# CON_REVC.net
KiCad netlist of a schematic drawn in EAGLE
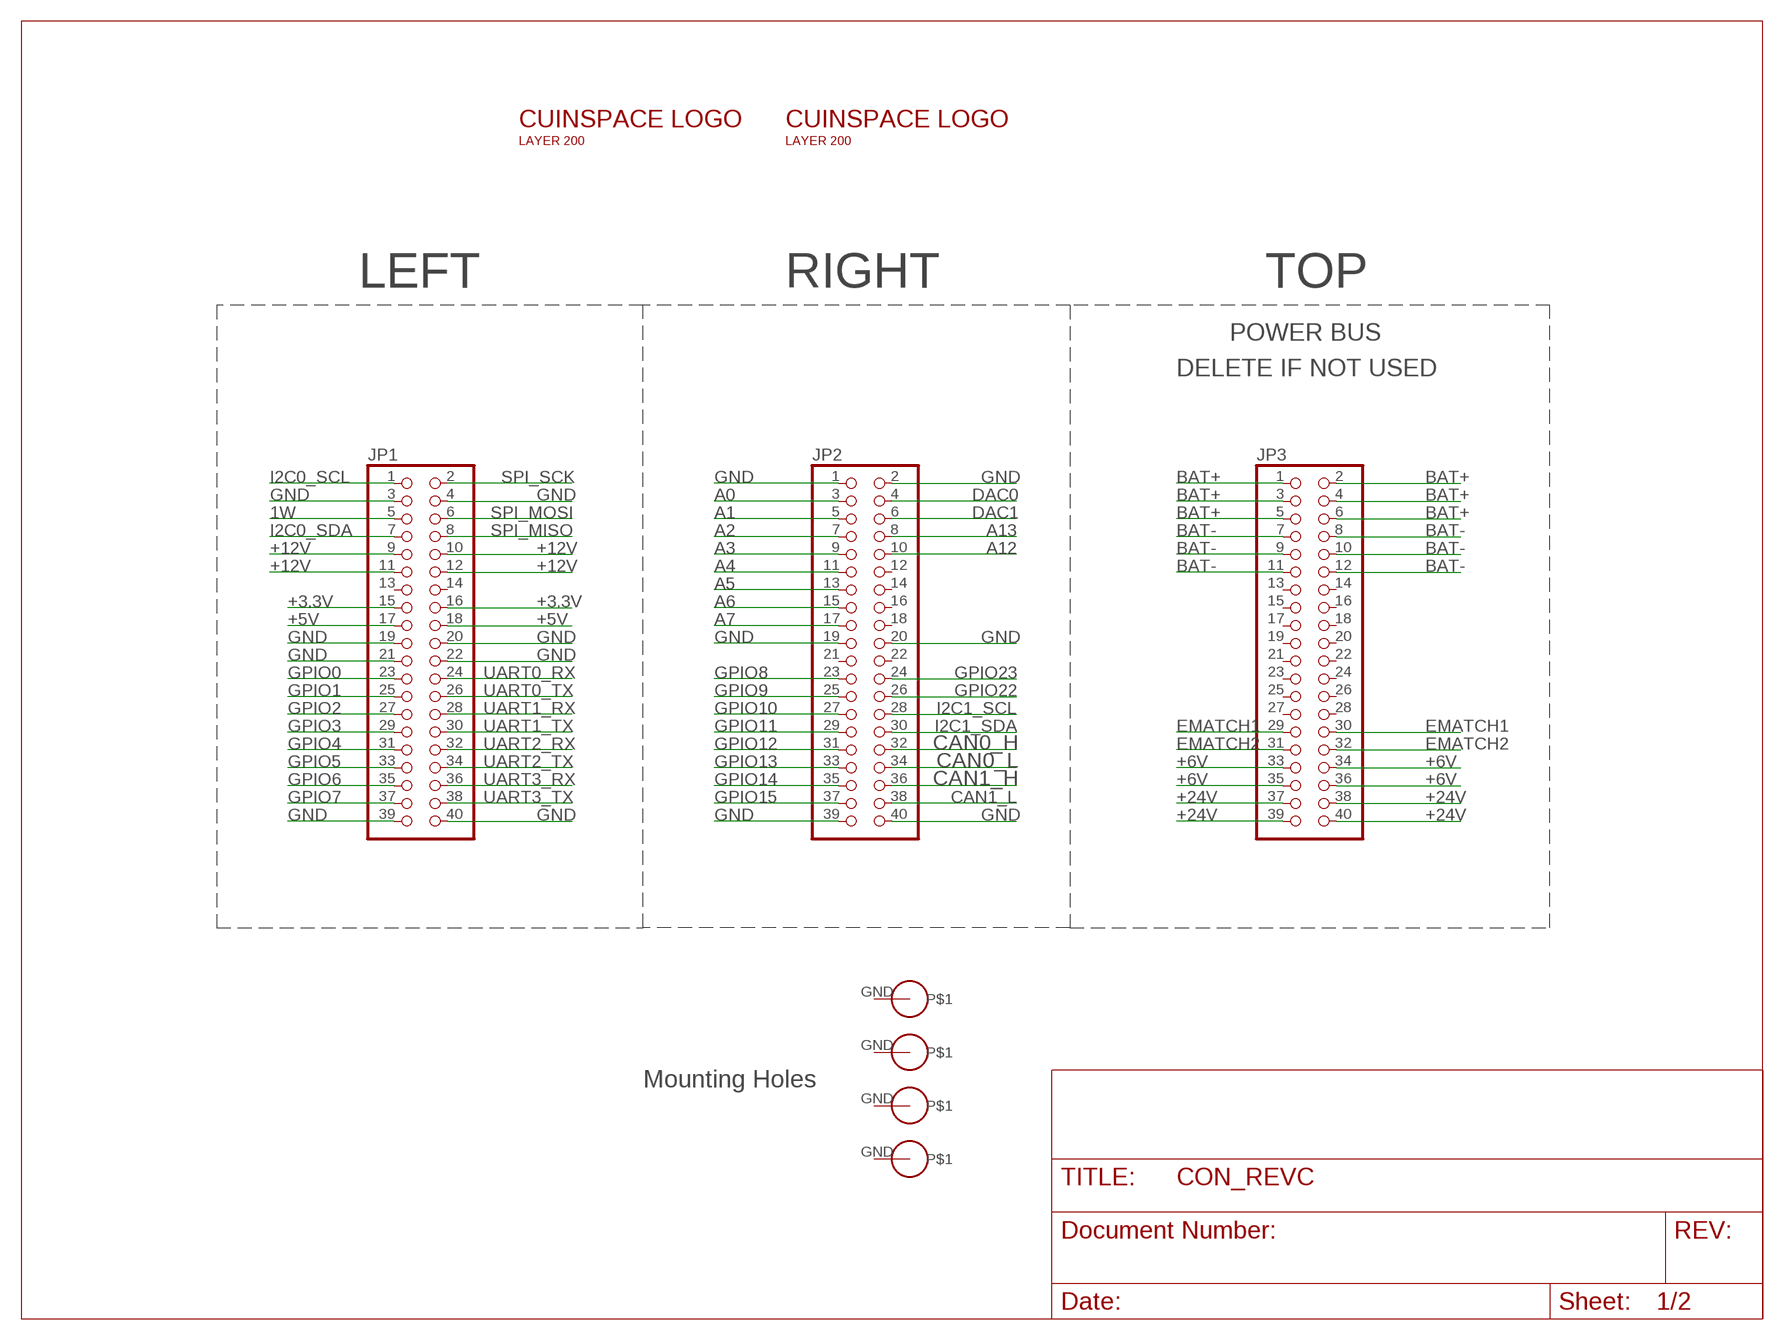
[diagram p0: schematic, sheet 1]
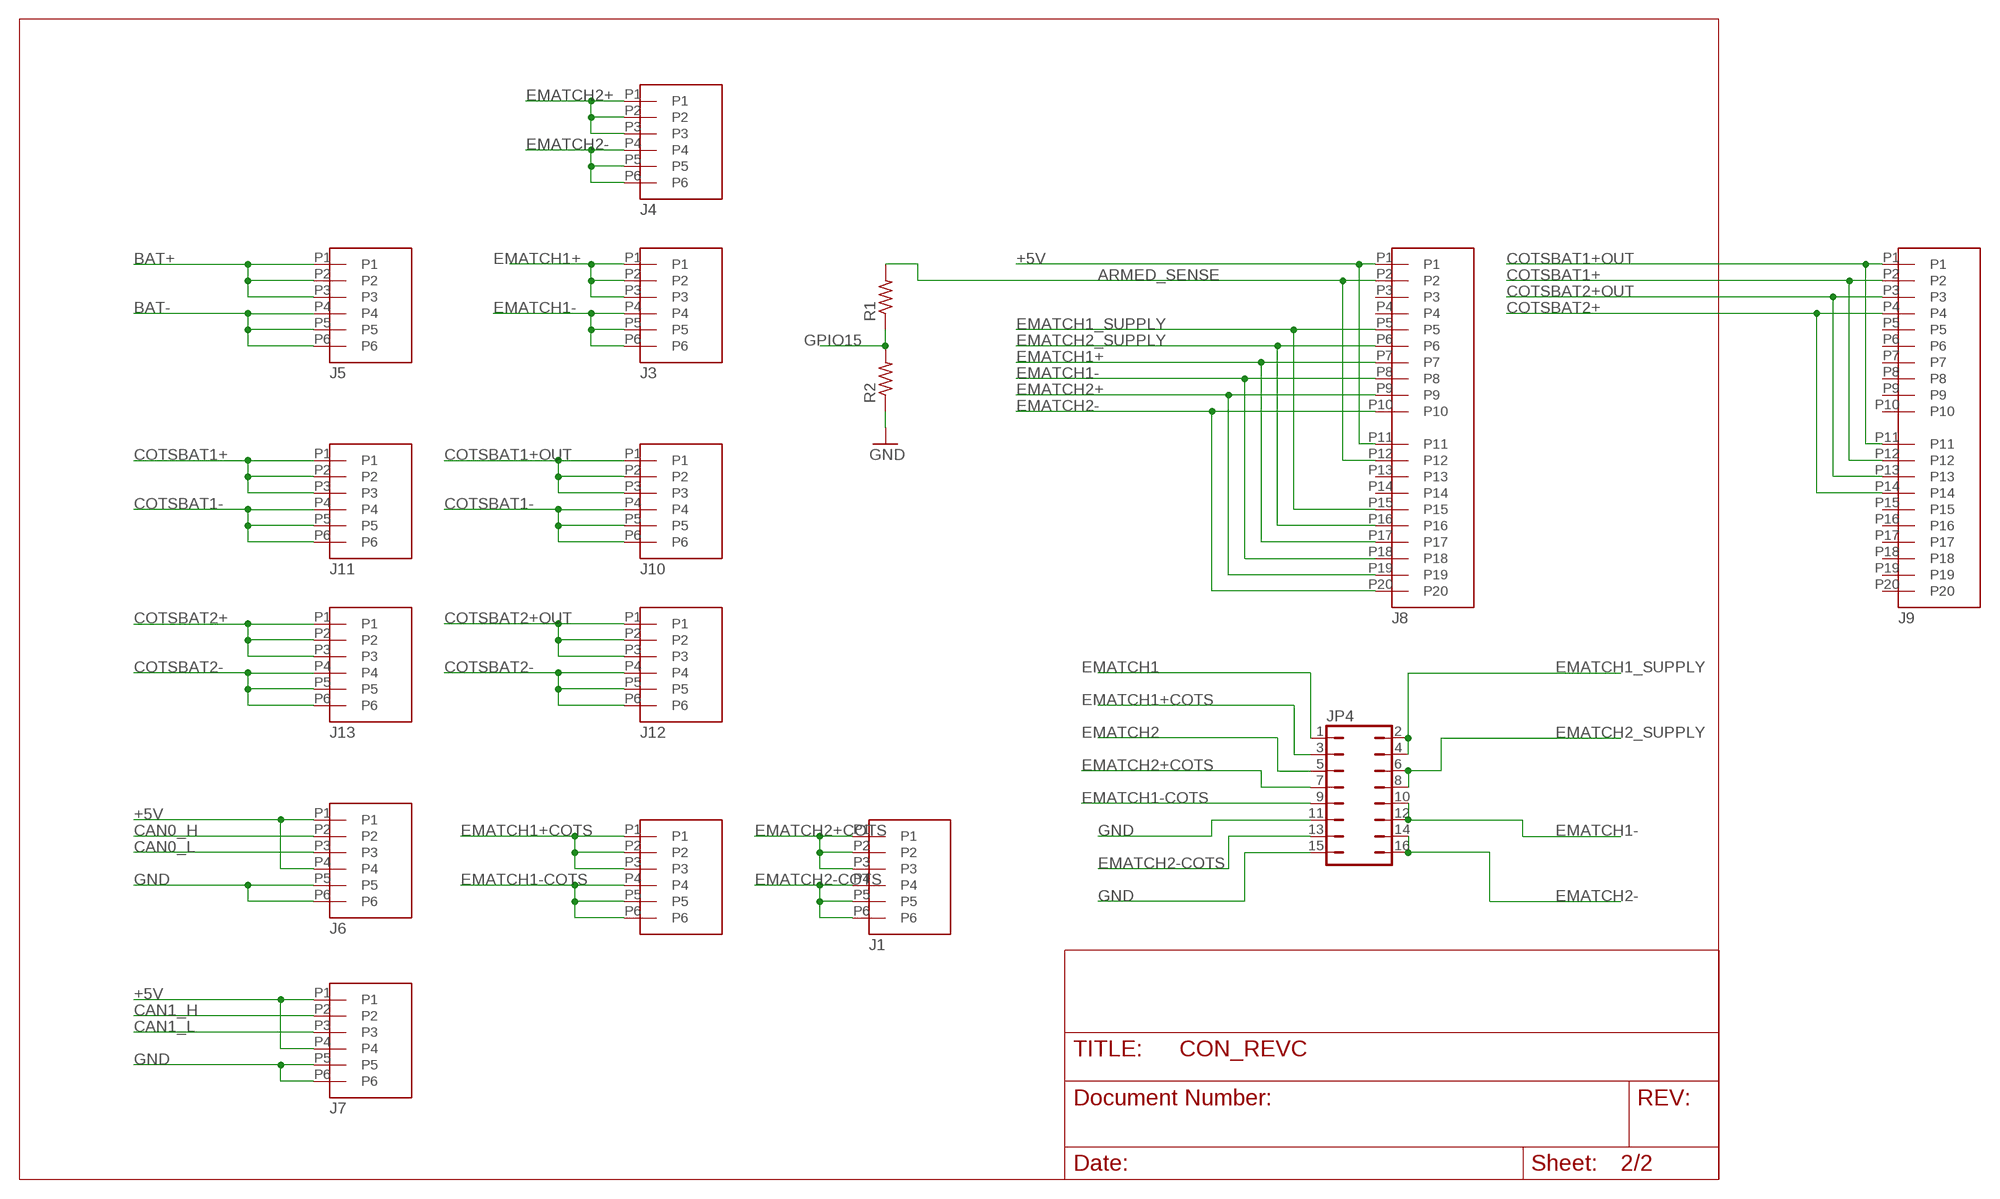
[diagram p1: schematic, sheet 2]

(export (version "E")
  (design (tool "Eeschema 10.0.6"))
  (components
    (comp (ref "$$U$1")
      (value "PS/104-MOUNTING-HOLE")
      (footprint "eagle-import:PC_104-MOUNTING-HOLE")
      (libsource (lib "eagle-import") (part "PS/104-MOUNTING-HOLE"))
    )
    (comp (ref "JP1")
      (value "PINHD-2X20")
      (footprint "eagle-import:2X20")
      (libsource (lib "eagle-import") (part "PINHD-2X20"))
    )
    (comp (ref "JP2")
      (value "PINHD-2X20")
      (footprint "eagle-import:2X20")
      (libsource (lib "eagle-import") (part "PINHD-2X20"))
    )
    (comp (ref "JP3")
      (value "PINHD-2X20")
      (footprint "eagle-import:2X20")
      (libsource (lib "eagle-import") (part "PINHD-2X20"))
    )
    (comp (ref "U$1")
      (value "PS/104-MOUNTING-HOLE")
      (footprint "eagle-import:PC_104-MOUNTING-HOLE")
      (libsource (lib "eagle-import") (part "PS/104-MOUNTING-HOLE"))
    )
    (comp (ref "U$2")
      (value "PS/104-MOUNTING-HOLE")
      (footprint "eagle-import:PC_104-MOUNTING-HOLE")
      (libsource (lib "eagle-import") (part "PS/104-MOUNTING-HOLE"))
    )
    (comp (ref "U$3")
      (value "PS/104-MOUNTING-HOLE")
      (footprint "eagle-import:PC_104-MOUNTING-HOLE")
      (libsource (lib "eagle-import") (part "PS/104-MOUNTING-HOLE"))
    )
    (comp (ref "U$5")
      (value "INSPACE3CM_L")
      (footprint "eagle-import:INSPACE_3CM_LETTERS")
      (libsource (lib "eagle-import") (part "INSPACE3CM_L"))
    )
    (comp (ref "U$6")
      (value "INSPACE3CM_L")
      (footprint "eagle-import:INSPACE_3CM_LETTERS")
      (libsource (lib "eagle-import") (part "INSPACE3CM_L"))
    )
    (comp (ref "J1")
      (value "M80-5100642")
      (footprint "eagle-import:M80-5100642")
      (libsource (lib "eagle-import") (part "M80-5100642"))
    )
    (comp (ref "J2")
      (value "M80-5100642")
      (footprint "eagle-import:M80-5100642")
      (libsource (lib "eagle-import") (part "M80-5100642"))
    )
    (comp (ref "J3")
      (value "M80-5100642")
      (footprint "eagle-import:M80-5100642")
      (libsource (lib "eagle-import") (part "M80-5100642"))
    )
    (comp (ref "J4")
      (value "M80-5100642")
      (footprint "eagle-import:M80-5100642")
      (libsource (lib "eagle-import") (part "M80-5100642"))
    )
    (comp (ref "J5")
      (value "M80-5100642")
      (footprint "eagle-import:M80-5100642")
      (libsource (lib "eagle-import") (part "M80-5100642"))
    )
    (comp (ref "J6")
      (value "M80-5100642")
      (footprint "eagle-import:M80-5100642")
      (libsource (lib "eagle-import") (part "M80-5100642"))
    )
    (comp (ref "J7")
      (value "M80-5100642")
      (footprint "eagle-import:M80-5100642")
      (libsource (lib "eagle-import") (part "M80-5100642"))
    )
    (comp (ref "J8")
      (value "M80-5102042")
      (footprint "eagle-import:M80-5102042")
      (libsource (lib "eagle-import") (part "M80-5102042"))
    )
    (comp (ref "J9")
      (value "M80-5102042")
      (footprint "eagle-import:M80-5102042")
      (libsource (lib "eagle-import") (part "M80-5102042"))
    )
    (comp (ref "J10")
      (value "M80-5100642")
      (footprint "eagle-import:M80-5100642")
      (libsource (lib "eagle-import") (part "M80-5100642"))
    )
    (comp (ref "J11")
      (value "M80-5100642")
      (footprint "eagle-import:M80-5100642")
      (libsource (lib "eagle-import") (part "M80-5100642"))
    )
    (comp (ref "J12")
      (value "M80-5100642")
      (footprint "eagle-import:M80-5100642")
      (libsource (lib "eagle-import") (part "M80-5100642"))
    )
    (comp (ref "J13")
      (value "M80-5100642")
      (footprint "eagle-import:M80-5100642")
      (libsource (lib "eagle-import") (part "M80-5100642"))
    )
    (comp (ref "JP4")
      (value "JP8Q")
      (footprint "eagle-import:JP8Q")
      (libsource (lib "eagle-import") (part "JP8Q"))
    )
    (comp (ref "R1")
      (value "R-US_R0805")
      (footprint "eagle-import:R0805")
      (libsource (lib "eagle-import") (part "R-US_R0805"))
    )
    (comp (ref "R2")
      (value "R-US_R0805")
      (footprint "eagle-import:R0805")
      (libsource (lib "eagle-import") (part "R-US_R0805"))
    )
  )
  (nets
    (net (code "1") (name "+3.3V") (class "Default")
      (node (ref "JP1") (pin "15") (pinfunction "15_15") (pintype "passive"))
      (node (ref "JP1") (pin "16") (pinfunction "16_16") (pintype "passive"))
    )
    (net (code "2") (name "+5V") (class "Default")
      (node (ref "J6") (pin "P1") (pinfunction "P1_P1") (pintype "bidirectional"))
      (node (ref "J6") (pin "P4") (pinfunction "P4_P4") (pintype "bidirectional"))
      (node (ref "J7") (pin "P1") (pinfunction "P1_P1") (pintype "bidirectional"))
      (node (ref "J7") (pin "P4") (pinfunction "P4_P4") (pintype "bidirectional"))
      (node (ref "J8") (pin "P1") (pinfunction "P1_P1") (pintype "bidirectional"))
      (node (ref "J8") (pin "P11") (pinfunction "P11_P11") (pintype "bidirectional"))
      (node (ref "JP1") (pin "17") (pinfunction "17_17") (pintype "passive"))
      (node (ref "JP1") (pin "18") (pinfunction "18_18") (pintype "passive"))
    )
    (net (code "3") (name "+6V") (class "Default")
      (node (ref "JP3") (pin "33") (pinfunction "33_33") (pintype "passive"))
      (node (ref "JP3") (pin "34") (pinfunction "34_34") (pintype "passive"))
      (node (ref "JP3") (pin "35") (pinfunction "35_35") (pintype "passive"))
      (node (ref "JP3") (pin "36") (pinfunction "36_36") (pintype "passive"))
    )
    (net (code "4") (name "+12V") (class "Default")
      (node (ref "JP1") (pin "10") (pinfunction "10_10") (pintype "passive"))
      (node (ref "JP1") (pin "11") (pinfunction "11_11") (pintype "passive"))
      (node (ref "JP1") (pin "12") (pinfunction "12_12") (pintype "passive"))
      (node (ref "JP1") (pin "9") (pinfunction "9_9") (pintype "passive"))
    )
    (net (code "5") (name "+24V") (class "Default")
      (node (ref "JP3") (pin "37") (pinfunction "37_37") (pintype "passive"))
      (node (ref "JP3") (pin "38") (pinfunction "38_38") (pintype "passive"))
      (node (ref "JP3") (pin "39") (pinfunction "39_39") (pintype "passive"))
      (node (ref "JP3") (pin "40") (pinfunction "40_40") (pintype "passive"))
    )
    (net (code "6") (name "1W") (class "Default")
      (node (ref "JP1") (pin "5") (pinfunction "5_5") (pintype "passive"))
    )
    (net (code "7") (name "A0") (class "Default")
      (node (ref "JP2") (pin "3") (pinfunction "3_3") (pintype "passive"))
    )
    (net (code "8") (name "A1") (class "Default")
      (node (ref "JP2") (pin "5") (pinfunction "5_5") (pintype "passive"))
    )
    (net (code "9") (name "A2") (class "Default")
      (node (ref "JP2") (pin "7") (pinfunction "7_7") (pintype "passive"))
    )
    (net (code "10") (name "A3") (class "Default")
      (node (ref "JP2") (pin "9") (pinfunction "9_9") (pintype "passive"))
    )
    (net (code "11") (name "A4") (class "Default")
      (node (ref "JP2") (pin "11") (pinfunction "11_11") (pintype "passive"))
    )
    (net (code "12") (name "A5") (class "Default")
      (node (ref "JP2") (pin "13") (pinfunction "13_13") (pintype "passive"))
    )
    (net (code "13") (name "A6") (class "Default")
      (node (ref "JP2") (pin "15") (pinfunction "15_15") (pintype "passive"))
    )
    (net (code "14") (name "A7") (class "Default")
      (node (ref "JP2") (pin "17") (pinfunction "17_17") (pintype "passive"))
    )
    (net (code "15") (name "A12") (class "Default")
      (node (ref "JP2") (pin "10") (pinfunction "10_10") (pintype "passive"))
    )
    (net (code "16") (name "A13") (class "Default")
      (node (ref "JP2") (pin "8") (pinfunction "8_8") (pintype "passive"))
    )
    (net (code "17") (name "ARMED_SENSE") (class "Default")
      (node (ref "J8") (pin "P12") (pinfunction "P12_P12") (pintype "bidirectional"))
      (node (ref "J8") (pin "P2") (pinfunction "P2_P2") (pintype "bidirectional"))
      (node (ref "R1") (pin "2") (pinfunction "2_2") (pintype "passive"))
    )
    (net (code "18") (name "BAT+") (class "Default")
      (node (ref "J5") (pin "P1") (pinfunction "P1_P1") (pintype "bidirectional"))
      (node (ref "J5") (pin "P2") (pinfunction "P2_P2") (pintype "bidirectional"))
      (node (ref "J5") (pin "P3") (pinfunction "P3_P3") (pintype "bidirectional"))
      (node (ref "JP3") (pin "1") (pinfunction "1_1") (pintype "passive"))
      (node (ref "JP3") (pin "2") (pinfunction "2_2") (pintype "passive"))
      (node (ref "JP3") (pin "3") (pinfunction "3_3") (pintype "passive"))
      (node (ref "JP3") (pin "4") (pinfunction "4_4") (pintype "passive"))
      (node (ref "JP3") (pin "5") (pinfunction "5_5") (pintype "passive"))
      (node (ref "JP3") (pin "6") (pinfunction "6_6") (pintype "passive"))
    )
    (net (code "19") (name "BAT-") (class "Default")
      (node (ref "J5") (pin "P4") (pinfunction "P4_P4") (pintype "bidirectional"))
      (node (ref "J5") (pin "P5") (pinfunction "P5_P5") (pintype "bidirectional"))
      (node (ref "J5") (pin "P6") (pinfunction "P6_P6") (pintype "bidirectional"))
      (node (ref "JP3") (pin "10") (pinfunction "10_10") (pintype "passive"))
      (node (ref "JP3") (pin "11") (pinfunction "11_11") (pintype "passive"))
      (node (ref "JP3") (pin "12") (pinfunction "12_12") (pintype "passive"))
      (node (ref "JP3") (pin "7") (pinfunction "7_7") (pintype "passive"))
      (node (ref "JP3") (pin "8") (pinfunction "8_8") (pintype "passive"))
      (node (ref "JP3") (pin "9") (pinfunction "9_9") (pintype "passive"))
    )
    (net (code "20") (name "CAN0_H") (class "Default")
      (node (ref "J6") (pin "P2") (pinfunction "P2_P2") (pintype "bidirectional"))
      (node (ref "JP2") (pin "32") (pinfunction "32_32") (pintype "passive"))
    )
    (net (code "21") (name "CAN0_L") (class "Default")
      (node (ref "J6") (pin "P3") (pinfunction "P3_P3") (pintype "bidirectional"))
      (node (ref "JP2") (pin "34") (pinfunction "34_34") (pintype "passive"))
    )
    (net (code "22") (name "CAN1_H") (class "Default")
      (node (ref "J7") (pin "P2") (pinfunction "P2_P2") (pintype "bidirectional"))
      (node (ref "JP2") (pin "36") (pinfunction "36_36") (pintype "passive"))
    )
    (net (code "23") (name "CAN1_L") (class "Default")
      (node (ref "J7") (pin "P3") (pinfunction "P3_P3") (pintype "bidirectional"))
      (node (ref "JP2") (pin "38") (pinfunction "38_38") (pintype "passive"))
    )
    (net (code "24") (name "COTSBAT1+") (class "Default")
      (node (ref "J11") (pin "P1") (pinfunction "P1_P1") (pintype "bidirectional"))
      (node (ref "J11") (pin "P2") (pinfunction "P2_P2") (pintype "bidirectional"))
      (node (ref "J11") (pin "P3") (pinfunction "P3_P3") (pintype "bidirectional"))
      (node (ref "J9") (pin "P12") (pinfunction "P12_P12") (pintype "bidirectional"))
      (node (ref "J9") (pin "P2") (pinfunction "P2_P2") (pintype "bidirectional"))
    )
    (net (code "25") (name "COTSBAT1+OUT") (class "Default")
      (node (ref "J10") (pin "P1") (pinfunction "P1_P1") (pintype "bidirectional"))
      (node (ref "J10") (pin "P2") (pinfunction "P2_P2") (pintype "bidirectional"))
      (node (ref "J10") (pin "P3") (pinfunction "P3_P3") (pintype "bidirectional"))
      (node (ref "J9") (pin "P1") (pinfunction "P1_P1") (pintype "bidirectional"))
      (node (ref "J9") (pin "P11") (pinfunction "P11_P11") (pintype "bidirectional"))
    )
    (net (code "26") (name "COTSBAT1-") (class "Default")
      (node (ref "J10") (pin "P4") (pinfunction "P4_P4") (pintype "bidirectional"))
      (node (ref "J10") (pin "P5") (pinfunction "P5_P5") (pintype "bidirectional"))
      (node (ref "J10") (pin "P6") (pinfunction "P6_P6") (pintype "bidirectional"))
      (node (ref "J11") (pin "P4") (pinfunction "P4_P4") (pintype "bidirectional"))
      (node (ref "J11") (pin "P5") (pinfunction "P5_P5") (pintype "bidirectional"))
      (node (ref "J11") (pin "P6") (pinfunction "P6_P6") (pintype "bidirectional"))
    )
    (net (code "27") (name "COTSBAT2+") (class "Default")
      (node (ref "J13") (pin "P1") (pinfunction "P1_P1") (pintype "bidirectional"))
      (node (ref "J13") (pin "P2") (pinfunction "P2_P2") (pintype "bidirectional"))
      (node (ref "J13") (pin "P3") (pinfunction "P3_P3") (pintype "bidirectional"))
      (node (ref "J9") (pin "P14") (pinfunction "P14_P14") (pintype "bidirectional"))
      (node (ref "J9") (pin "P4") (pinfunction "P4_P4") (pintype "bidirectional"))
    )
    (net (code "28") (name "COTSBAT2+OUT") (class "Default")
      (node (ref "J12") (pin "P1") (pinfunction "P1_P1") (pintype "bidirectional"))
      (node (ref "J12") (pin "P2") (pinfunction "P2_P2") (pintype "bidirectional"))
      (node (ref "J12") (pin "P3") (pinfunction "P3_P3") (pintype "bidirectional"))
      (node (ref "J9") (pin "P13") (pinfunction "P13_P13") (pintype "bidirectional"))
      (node (ref "J9") (pin "P3") (pinfunction "P3_P3") (pintype "bidirectional"))
    )
    (net (code "29") (name "COTSBAT2-") (class "Default")
      (node (ref "J12") (pin "P4") (pinfunction "P4_P4") (pintype "bidirectional"))
      (node (ref "J12") (pin "P5") (pinfunction "P5_P5") (pintype "bidirectional"))
      (node (ref "J12") (pin "P6") (pinfunction "P6_P6") (pintype "bidirectional"))
      (node (ref "J13") (pin "P4") (pinfunction "P4_P4") (pintype "bidirectional"))
      (node (ref "J13") (pin "P5") (pinfunction "P5_P5") (pintype "bidirectional"))
      (node (ref "J13") (pin "P6") (pinfunction "P6_P6") (pintype "bidirectional"))
    )
    (net (code "30") (name "DAC0") (class "Default")
      (node (ref "JP2") (pin "4") (pinfunction "4_4") (pintype "passive"))
    )
    (net (code "31") (name "DAC1") (class "Default")
      (node (ref "JP2") (pin "6") (pinfunction "6_6") (pintype "passive"))
    )
    (net (code "32") (name "EMATCH1") (class "Default")
      (node (ref "JP3") (pin "29") (pinfunction "29_29") (pintype "passive"))
      (node (ref "JP3") (pin "30") (pinfunction "30_30") (pintype "passive"))
      (node (ref "JP4") (pin "1") (pinfunction "1_1") (pintype "passive"))
    )
    (net (code "33") (name "EMATCH1+") (class "Default")
      (node (ref "J3") (pin "P1") (pinfunction "P1_P1") (pintype "bidirectional"))
      (node (ref "J3") (pin "P2") (pinfunction "P2_P2") (pintype "bidirectional"))
      (node (ref "J3") (pin "P3") (pinfunction "P3_P3") (pintype "bidirectional"))
      (node (ref "J8") (pin "P17") (pinfunction "P17_P17") (pintype "bidirectional"))
      (node (ref "J8") (pin "P7") (pinfunction "P7_P7") (pintype "bidirectional"))
    )
    (net (code "34") (name "EMATCH1+COTS") (class "Default")
      (node (ref "J2") (pin "P1") (pinfunction "P1_P1") (pintype "bidirectional"))
      (node (ref "J2") (pin "P2") (pinfunction "P2_P2") (pintype "bidirectional"))
      (node (ref "J2") (pin "P3") (pinfunction "P3_P3") (pintype "bidirectional"))
      (node (ref "JP4") (pin "3") (pinfunction "3_3") (pintype "passive"))
    )
    (net (code "35") (name "EMATCH1-") (class "Default")
      (node (ref "J3") (pin "P4") (pinfunction "P4_P4") (pintype "bidirectional"))
      (node (ref "J3") (pin "P5") (pinfunction "P5_P5") (pintype "bidirectional"))
      (node (ref "J3") (pin "P6") (pinfunction "P6_P6") (pintype "bidirectional"))
      (node (ref "J8") (pin "P18") (pinfunction "P18_P18") (pintype "bidirectional"))
      (node (ref "J8") (pin "P8") (pinfunction "P8_P8") (pintype "bidirectional"))
      (node (ref "JP4") (pin "10") (pinfunction "10_10") (pintype "passive"))
      (node (ref "JP4") (pin "12") (pinfunction "12_12") (pintype "passive"))
    )
    (net (code "36") (name "EMATCH1-COTS") (class "Default")
      (node (ref "J2") (pin "P4") (pinfunction "P4_P4") (pintype "bidirectional"))
      (node (ref "J2") (pin "P5") (pinfunction "P5_P5") (pintype "bidirectional"))
      (node (ref "J2") (pin "P6") (pinfunction "P6_P6") (pintype "bidirectional"))
      (node (ref "JP4") (pin "9") (pinfunction "9_9") (pintype "passive"))
    )
    (net (code "37") (name "EMATCH1_SUPPLY") (class "Default")
      (node (ref "J8") (pin "P15") (pinfunction "P15_P15") (pintype "bidirectional"))
      (node (ref "J8") (pin "P5") (pinfunction "P5_P5") (pintype "bidirectional"))
      (node (ref "JP4") (pin "2") (pinfunction "2_2") (pintype "passive"))
      (node (ref "JP4") (pin "4") (pinfunction "4_4") (pintype "passive"))
    )
    (net (code "38") (name "EMATCH2") (class "Default")
      (node (ref "JP3") (pin "31") (pinfunction "31_31") (pintype "passive"))
      (node (ref "JP3") (pin "32") (pinfunction "32_32") (pintype "passive"))
      (node (ref "JP4") (pin "5") (pinfunction "5_5") (pintype "passive"))
    )
    (net (code "39") (name "EMATCH2+") (class "Default")
      (node (ref "J4") (pin "P1") (pinfunction "P1_P1") (pintype "bidirectional"))
      (node (ref "J4") (pin "P2") (pinfunction "P2_P2") (pintype "bidirectional"))
      (node (ref "J4") (pin "P3") (pinfunction "P3_P3") (pintype "bidirectional"))
      (node (ref "J8") (pin "P19") (pinfunction "P19_P19") (pintype "bidirectional"))
      (node (ref "J8") (pin "P9") (pinfunction "P9_P9") (pintype "bidirectional"))
    )
    (net (code "40") (name "EMATCH2+COTS") (class "Default")
      (node (ref "J1") (pin "P1") (pinfunction "P1_P1") (pintype "bidirectional"))
      (node (ref "J1") (pin "P2") (pinfunction "P2_P2") (pintype "bidirectional"))
      (node (ref "J1") (pin "P3") (pinfunction "P3_P3") (pintype "bidirectional"))
      (node (ref "JP4") (pin "7") (pinfunction "7_7") (pintype "passive"))
    )
    (net (code "41") (name "EMATCH2-") (class "Default")
      (node (ref "J4") (pin "P4") (pinfunction "P4_P4") (pintype "bidirectional"))
      (node (ref "J4") (pin "P5") (pinfunction "P5_P5") (pintype "bidirectional"))
      (node (ref "J4") (pin "P6") (pinfunction "P6_P6") (pintype "bidirectional"))
      (node (ref "J8") (pin "P10") (pinfunction "P10_P10") (pintype "bidirectional"))
      (node (ref "J8") (pin "P20") (pinfunction "P20_P20") (pintype "bidirectional"))
      (node (ref "JP4") (pin "14") (pinfunction "14_14") (pintype "passive"))
      (node (ref "JP4") (pin "16") (pinfunction "16_16") (pintype "passive"))
    )
    (net (code "42") (name "EMATCH2-COTS") (class "Default")
      (node (ref "J1") (pin "P4") (pinfunction "P4_P4") (pintype "bidirectional"))
      (node (ref "J1") (pin "P5") (pinfunction "P5_P5") (pintype "bidirectional"))
      (node (ref "J1") (pin "P6") (pinfunction "P6_P6") (pintype "bidirectional"))
      (node (ref "JP4") (pin "13") (pinfunction "13_13") (pintype "passive"))
    )
    (net (code "43") (name "EMATCH2_SUPPLY") (class "Default")
      (node (ref "J8") (pin "P16") (pinfunction "P16_P16") (pintype "bidirectional"))
      (node (ref "J8") (pin "P6") (pinfunction "P6_P6") (pintype "bidirectional"))
      (node (ref "JP4") (pin "6") (pinfunction "6_6") (pintype "passive"))
      (node (ref "JP4") (pin "8") (pinfunction "8_8") (pintype "passive"))
    )
    (net (code "44") (name "GND") (class "Default")
      (node (ref "J6") (pin "P5") (pinfunction "P5_P5") (pintype "bidirectional"))
      (node (ref "J6") (pin "P6") (pinfunction "P6_P6") (pintype "bidirectional"))
      (node (ref "J7") (pin "P5") (pinfunction "P5_P5") (pintype "bidirectional"))
      (node (ref "J7") (pin "P6") (pinfunction "P6_P6") (pintype "bidirectional"))
      (node (ref "JP1") (pin "19") (pinfunction "19_19") (pintype "passive"))
      (node (ref "JP1") (pin "20") (pinfunction "20_20") (pintype "passive"))
      (node (ref "JP1") (pin "21") (pinfunction "21_21") (pintype "passive"))
      (node (ref "JP1") (pin "22") (pinfunction "22_22") (pintype "passive"))
      (node (ref "JP1") (pin "3") (pinfunction "3_3") (pintype "passive"))
      (node (ref "JP1") (pin "39") (pinfunction "39_39") (pintype "passive"))
      (node (ref "JP1") (pin "4") (pinfunction "4_4") (pintype "passive"))
      (node (ref "JP1") (pin "40") (pinfunction "40_40") (pintype "passive"))
      (node (ref "JP2") (pin "1") (pinfunction "1_1") (pintype "passive"))
      (node (ref "JP2") (pin "19") (pinfunction "19_19") (pintype "passive"))
      (node (ref "JP2") (pin "2") (pinfunction "2_2") (pintype "passive"))
      (node (ref "JP2") (pin "20") (pinfunction "20_20") (pintype "passive"))
      (node (ref "JP2") (pin "39") (pinfunction "39_39") (pintype "passive"))
      (node (ref "JP2") (pin "40") (pinfunction "40_40") (pintype "passive"))
      (node (ref "JP4") (pin "11") (pinfunction "11_11") (pintype "passive"))
      (node (ref "JP4") (pin "15") (pinfunction "15_15") (pintype "passive"))
      (node (ref "R2") (pin "1") (pinfunction "1_1") (pintype "passive"))
    )
    (net (code "45") (name "GPIO0") (class "Default")
      (node (ref "JP1") (pin "23") (pinfunction "23_23") (pintype "passive"))
    )
    (net (code "46") (name "GPIO1") (class "Default")
      (node (ref "JP1") (pin "25") (pinfunction "25_25") (pintype "passive"))
    )
    (net (code "47") (name "GPIO2") (class "Default")
      (node (ref "JP1") (pin "27") (pinfunction "27_27") (pintype "passive"))
    )
    (net (code "48") (name "GPIO3") (class "Default")
      (node (ref "JP1") (pin "29") (pinfunction "29_29") (pintype "passive"))
    )
    (net (code "49") (name "GPIO4") (class "Default")
      (node (ref "JP1") (pin "31") (pinfunction "31_31") (pintype "passive"))
    )
    (net (code "50") (name "GPIO5") (class "Default")
      (node (ref "JP1") (pin "33") (pinfunction "33_33") (pintype "passive"))
    )
    (net (code "51") (name "GPIO6") (class "Default")
      (node (ref "JP1") (pin "35") (pinfunction "35_35") (pintype "passive"))
    )
    (net (code "52") (name "GPIO7") (class "Default")
      (node (ref "JP1") (pin "37") (pinfunction "37_37") (pintype "passive"))
    )
    (net (code "53") (name "GPIO8") (class "Default")
      (node (ref "JP2") (pin "23") (pinfunction "23_23") (pintype "passive"))
    )
    (net (code "54") (name "GPIO9") (class "Default")
      (node (ref "JP2") (pin "25") (pinfunction "25_25") (pintype "passive"))
    )
    (net (code "55") (name "GPIO10") (class "Default")
      (node (ref "JP2") (pin "27") (pinfunction "27_27") (pintype "passive"))
    )
    (net (code "56") (name "GPIO11") (class "Default")
      (node (ref "JP2") (pin "29") (pinfunction "29_29") (pintype "passive"))
    )
    (net (code "57") (name "GPIO12") (class "Default")
      (node (ref "JP2") (pin "31") (pinfunction "31_31") (pintype "passive"))
    )
    (net (code "58") (name "GPIO13") (class "Default")
      (node (ref "JP2") (pin "33") (pinfunction "33_33") (pintype "passive"))
    )
    (net (code "59") (name "GPIO14") (class "Default")
      (node (ref "JP2") (pin "35") (pinfunction "35_35") (pintype "passive"))
    )
    (net (code "60") (name "GPIO15") (class "Default")
      (node (ref "JP2") (pin "37") (pinfunction "37_37") (pintype "passive"))
      (node (ref "R1") (pin "1") (pinfunction "1_1") (pintype "passive"))
      (node (ref "R2") (pin "2") (pinfunction "2_2") (pintype "passive"))
    )
    (net (code "61") (name "GPIO22") (class "Default")
      (node (ref "JP2") (pin "26") (pinfunction "26_26") (pintype "passive"))
    )
    (net (code "62") (name "GPIO23") (class "Default")
      (node (ref "JP2") (pin "24") (pinfunction "24_24") (pintype "passive"))
    )
    (net (code "63") (name "I2C0_SCL") (class "Default")
      (node (ref "JP1") (pin "1") (pinfunction "1_1") (pintype "passive"))
    )
    (net (code "64") (name "I2C0_SDA") (class "Default")
      (node (ref "JP1") (pin "7") (pinfunction "7_7") (pintype "passive"))
    )
    (net (code "65") (name "I2C1_SCL") (class "Default")
      (node (ref "JP2") (pin "28") (pinfunction "28_28") (pintype "passive"))
    )
    (net (code "66") (name "I2C1_SDA") (class "Default")
      (node (ref "JP2") (pin "30") (pinfunction "30_30") (pintype "passive"))
    )
    (net (code "67") (name "SPI_MISO") (class "Default")
      (node (ref "JP1") (pin "8") (pinfunction "8_8") (pintype "passive"))
    )
    (net (code "68") (name "SPI_MOSI") (class "Default")
      (node (ref "JP1") (pin "6") (pinfunction "6_6") (pintype "passive"))
    )
    (net (code "69") (name "SPI_SCK") (class "Default")
      (node (ref "JP1") (pin "2") (pinfunction "2_2") (pintype "passive"))
    )
    (net (code "70") (name "UART0_RX") (class "Default")
      (node (ref "JP1") (pin "24") (pinfunction "24_24") (pintype "passive"))
    )
    (net (code "71") (name "UART0_TX") (class "Default")
      (node (ref "JP1") (pin "26") (pinfunction "26_26") (pintype "passive"))
    )
    (net (code "72") (name "UART1_RX") (class "Default")
      (node (ref "JP1") (pin "28") (pinfunction "28_28") (pintype "passive"))
    )
    (net (code "73") (name "UART1_TX") (class "Default")
      (node (ref "JP1") (pin "30") (pinfunction "30_30") (pintype "passive"))
    )
    (net (code "74") (name "UART2_RX") (class "Default")
      (node (ref "JP1") (pin "32") (pinfunction "32_32") (pintype "passive"))
    )
    (net (code "75") (name "UART2_TX") (class "Default")
      (node (ref "JP1") (pin "34") (pinfunction "34_34") (pintype "passive"))
    )
    (net (code "76") (name "UART3_RX") (class "Default")
      (node (ref "JP1") (pin "36") (pinfunction "36_36") (pintype "passive"))
    )
    (net (code "77") (name "UART3_TX") (class "Default")
      (node (ref "JP1") (pin "38") (pinfunction "38_38") (pintype "passive"))
    )
    (net (code "78") (name "unconnected-($$U$1-P$1-PadGND)") (class "Default")
      (node (ref "$$U$1") (pin "GND") (pinfunction "P$1_GND") (pintype "bidirectional"))
    )
    (net (code "79") (name "unconnected-(J8-PadP3)") (class "Default")
      (node (ref "J8") (pin "P3") (pinfunction "P3_P3") (pintype "bidirectional"))
    )
    (net (code "80") (name "unconnected-(J8-PadP4)") (class "Default")
      (node (ref "J8") (pin "P4") (pinfunction "P4_P4") (pintype "bidirectional"))
    )
    (net (code "81") (name "unconnected-(J8-PadP13)") (class "Default")
      (node (ref "J8") (pin "P13") (pinfunction "P13_P13") (pintype "bidirectional"))
    )
    (net (code "82") (name "unconnected-(J8-PadP14)") (class "Default")
      (node (ref "J8") (pin "P14") (pinfunction "P14_P14") (pintype "bidirectional"))
    )
    (net (code "83") (name "unconnected-(J9-PadP5)") (class "Default")
      (node (ref "J9") (pin "P5") (pinfunction "P5_P5") (pintype "bidirectional"))
    )
    (net (code "84") (name "unconnected-(J9-PadP6)") (class "Default")
      (node (ref "J9") (pin "P6") (pinfunction "P6_P6") (pintype "bidirectional"))
    )
    (net (code "85") (name "unconnected-(J9-PadP7)") (class "Default")
      (node (ref "J9") (pin "P7") (pinfunction "P7_P7") (pintype "bidirectional"))
    )
    (net (code "86") (name "unconnected-(J9-PadP8)") (class "Default")
      (node (ref "J9") (pin "P8") (pinfunction "P8_P8") (pintype "bidirectional"))
    )
    (net (code "87") (name "unconnected-(J9-PadP9)") (class "Default")
      (node (ref "J9") (pin "P9") (pinfunction "P9_P9") (pintype "bidirectional"))
    )
    (net (code "88") (name "unconnected-(J9-PadP10)") (class "Default")
      (node (ref "J9") (pin "P10") (pinfunction "P10_P10") (pintype "bidirectional"))
    )
    (net (code "89") (name "unconnected-(J9-PadP15)") (class "Default")
      (node (ref "J9") (pin "P15") (pinfunction "P15_P15") (pintype "bidirectional"))
    )
    (net (code "90") (name "unconnected-(J9-PadP16)") (class "Default")
      (node (ref "J9") (pin "P16") (pinfunction "P16_P16") (pintype "bidirectional"))
    )
    (net (code "91") (name "unconnected-(J9-PadP17)") (class "Default")
      (node (ref "J9") (pin "P17") (pinfunction "P17_P17") (pintype "bidirectional"))
    )
    (net (code "92") (name "unconnected-(J9-PadP18)") (class "Default")
      (node (ref "J9") (pin "P18") (pinfunction "P18_P18") (pintype "bidirectional"))
    )
    (net (code "93") (name "unconnected-(J9-PadP19)") (class "Default")
      (node (ref "J9") (pin "P19") (pinfunction "P19_P19") (pintype "bidirectional"))
    )
    (net (code "94") (name "unconnected-(J9-PadP20)") (class "Default")
      (node (ref "J9") (pin "P20") (pinfunction "P20_P20") (pintype "bidirectional"))
    )
    (net (code "95") (name "unconnected-(JP1-Pad13)") (class "Default")
      (node (ref "JP1") (pin "13") (pinfunction "13_13") (pintype "passive"))
    )
    (net (code "96") (name "unconnected-(JP1-Pad14)") (class "Default")
      (node (ref "JP1") (pin "14") (pinfunction "14_14") (pintype "passive"))
    )
    (net (code "97") (name "unconnected-(JP2-Pad12)") (class "Default")
      (node (ref "JP2") (pin "12") (pinfunction "12_12") (pintype "passive"))
    )
    (net (code "98") (name "unconnected-(JP2-Pad14)") (class "Default")
      (node (ref "JP2") (pin "14") (pinfunction "14_14") (pintype "passive"))
    )
    (net (code "99") (name "unconnected-(JP2-Pad16)") (class "Default")
      (node (ref "JP2") (pin "16") (pinfunction "16_16") (pintype "passive"))
    )
    (net (code "100") (name "unconnected-(JP2-Pad18)") (class "Default")
      (node (ref "JP2") (pin "18") (pinfunction "18_18") (pintype "passive"))
    )
    (net (code "101") (name "unconnected-(JP2-Pad21)") (class "Default")
      (node (ref "JP2") (pin "21") (pinfunction "21_21") (pintype "passive"))
    )
    (net (code "102") (name "unconnected-(JP2-Pad22)") (class "Default")
      (node (ref "JP2") (pin "22") (pinfunction "22_22") (pintype "passive"))
    )
    (net (code "103") (name "unconnected-(JP3-Pad13)") (class "Default")
      (node (ref "JP3") (pin "13") (pinfunction "13_13") (pintype "passive"))
    )
    (net (code "104") (name "unconnected-(JP3-Pad14)") (class "Default")
      (node (ref "JP3") (pin "14") (pinfunction "14_14") (pintype "passive"))
    )
    (net (code "105") (name "unconnected-(JP3-Pad15)") (class "Default")
      (node (ref "JP3") (pin "15") (pinfunction "15_15") (pintype "passive"))
    )
    (net (code "106") (name "unconnected-(JP3-Pad16)") (class "Default")
      (node (ref "JP3") (pin "16") (pinfunction "16_16") (pintype "passive"))
    )
    (net (code "107") (name "unconnected-(JP3-Pad17)") (class "Default")
      (node (ref "JP3") (pin "17") (pinfunction "17_17") (pintype "passive"))
    )
    (net (code "108") (name "unconnected-(JP3-Pad18)") (class "Default")
      (node (ref "JP3") (pin "18") (pinfunction "18_18") (pintype "passive"))
    )
    (net (code "109") (name "unconnected-(JP3-Pad19)") (class "Default")
      (node (ref "JP3") (pin "19") (pinfunction "19_19") (pintype "passive"))
    )
    (net (code "110") (name "unconnected-(JP3-Pad20)") (class "Default")
      (node (ref "JP3") (pin "20") (pinfunction "20_20") (pintype "passive"))
    )
    (net (code "111") (name "unconnected-(JP3-Pad21)") (class "Default")
      (node (ref "JP3") (pin "21") (pinfunction "21_21") (pintype "passive"))
    )
    (net (code "112") (name "unconnected-(JP3-Pad22)") (class "Default")
      (node (ref "JP3") (pin "22") (pinfunction "22_22") (pintype "passive"))
    )
    (net (code "113") (name "unconnected-(JP3-Pad23)") (class "Default")
      (node (ref "JP3") (pin "23") (pinfunction "23_23") (pintype "passive"))
    )
    (net (code "114") (name "unconnected-(JP3-Pad24)") (class "Default")
      (node (ref "JP3") (pin "24") (pinfunction "24_24") (pintype "passive"))
    )
    (net (code "115") (name "unconnected-(JP3-Pad25)") (class "Default")
      (node (ref "JP3") (pin "25") (pinfunction "25_25") (pintype "passive"))
    )
    (net (code "116") (name "unconnected-(JP3-Pad26)") (class "Default")
      (node (ref "JP3") (pin "26") (pinfunction "26_26") (pintype "passive"))
    )
    (net (code "117") (name "unconnected-(JP3-Pad27)") (class "Default")
      (node (ref "JP3") (pin "27") (pinfunction "27_27") (pintype "passive"))
    )
    (net (code "118") (name "unconnected-(JP3-Pad28)") (class "Default")
      (node (ref "JP3") (pin "28") (pinfunction "28_28") (pintype "passive"))
    )
    (net (code "119") (name "unconnected-(U$1-P$1-PadGND)") (class "Default")
      (node (ref "U$1") (pin "GND") (pinfunction "P$1_GND") (pintype "bidirectional"))
    )
    (net (code "120") (name "unconnected-(U$2-P$1-PadGND)") (class "Default")
      (node (ref "U$2") (pin "GND") (pinfunction "P$1_GND") (pintype "bidirectional"))
    )
    (net (code "121") (name "unconnected-(U$3-P$1-PadGND)") (class "Default")
      (node (ref "U$3") (pin "GND") (pinfunction "P$1_GND") (pintype "bidirectional"))
    )
  )
)
